# main.net
KiCad netlist of a schematic drawn in EAGLE
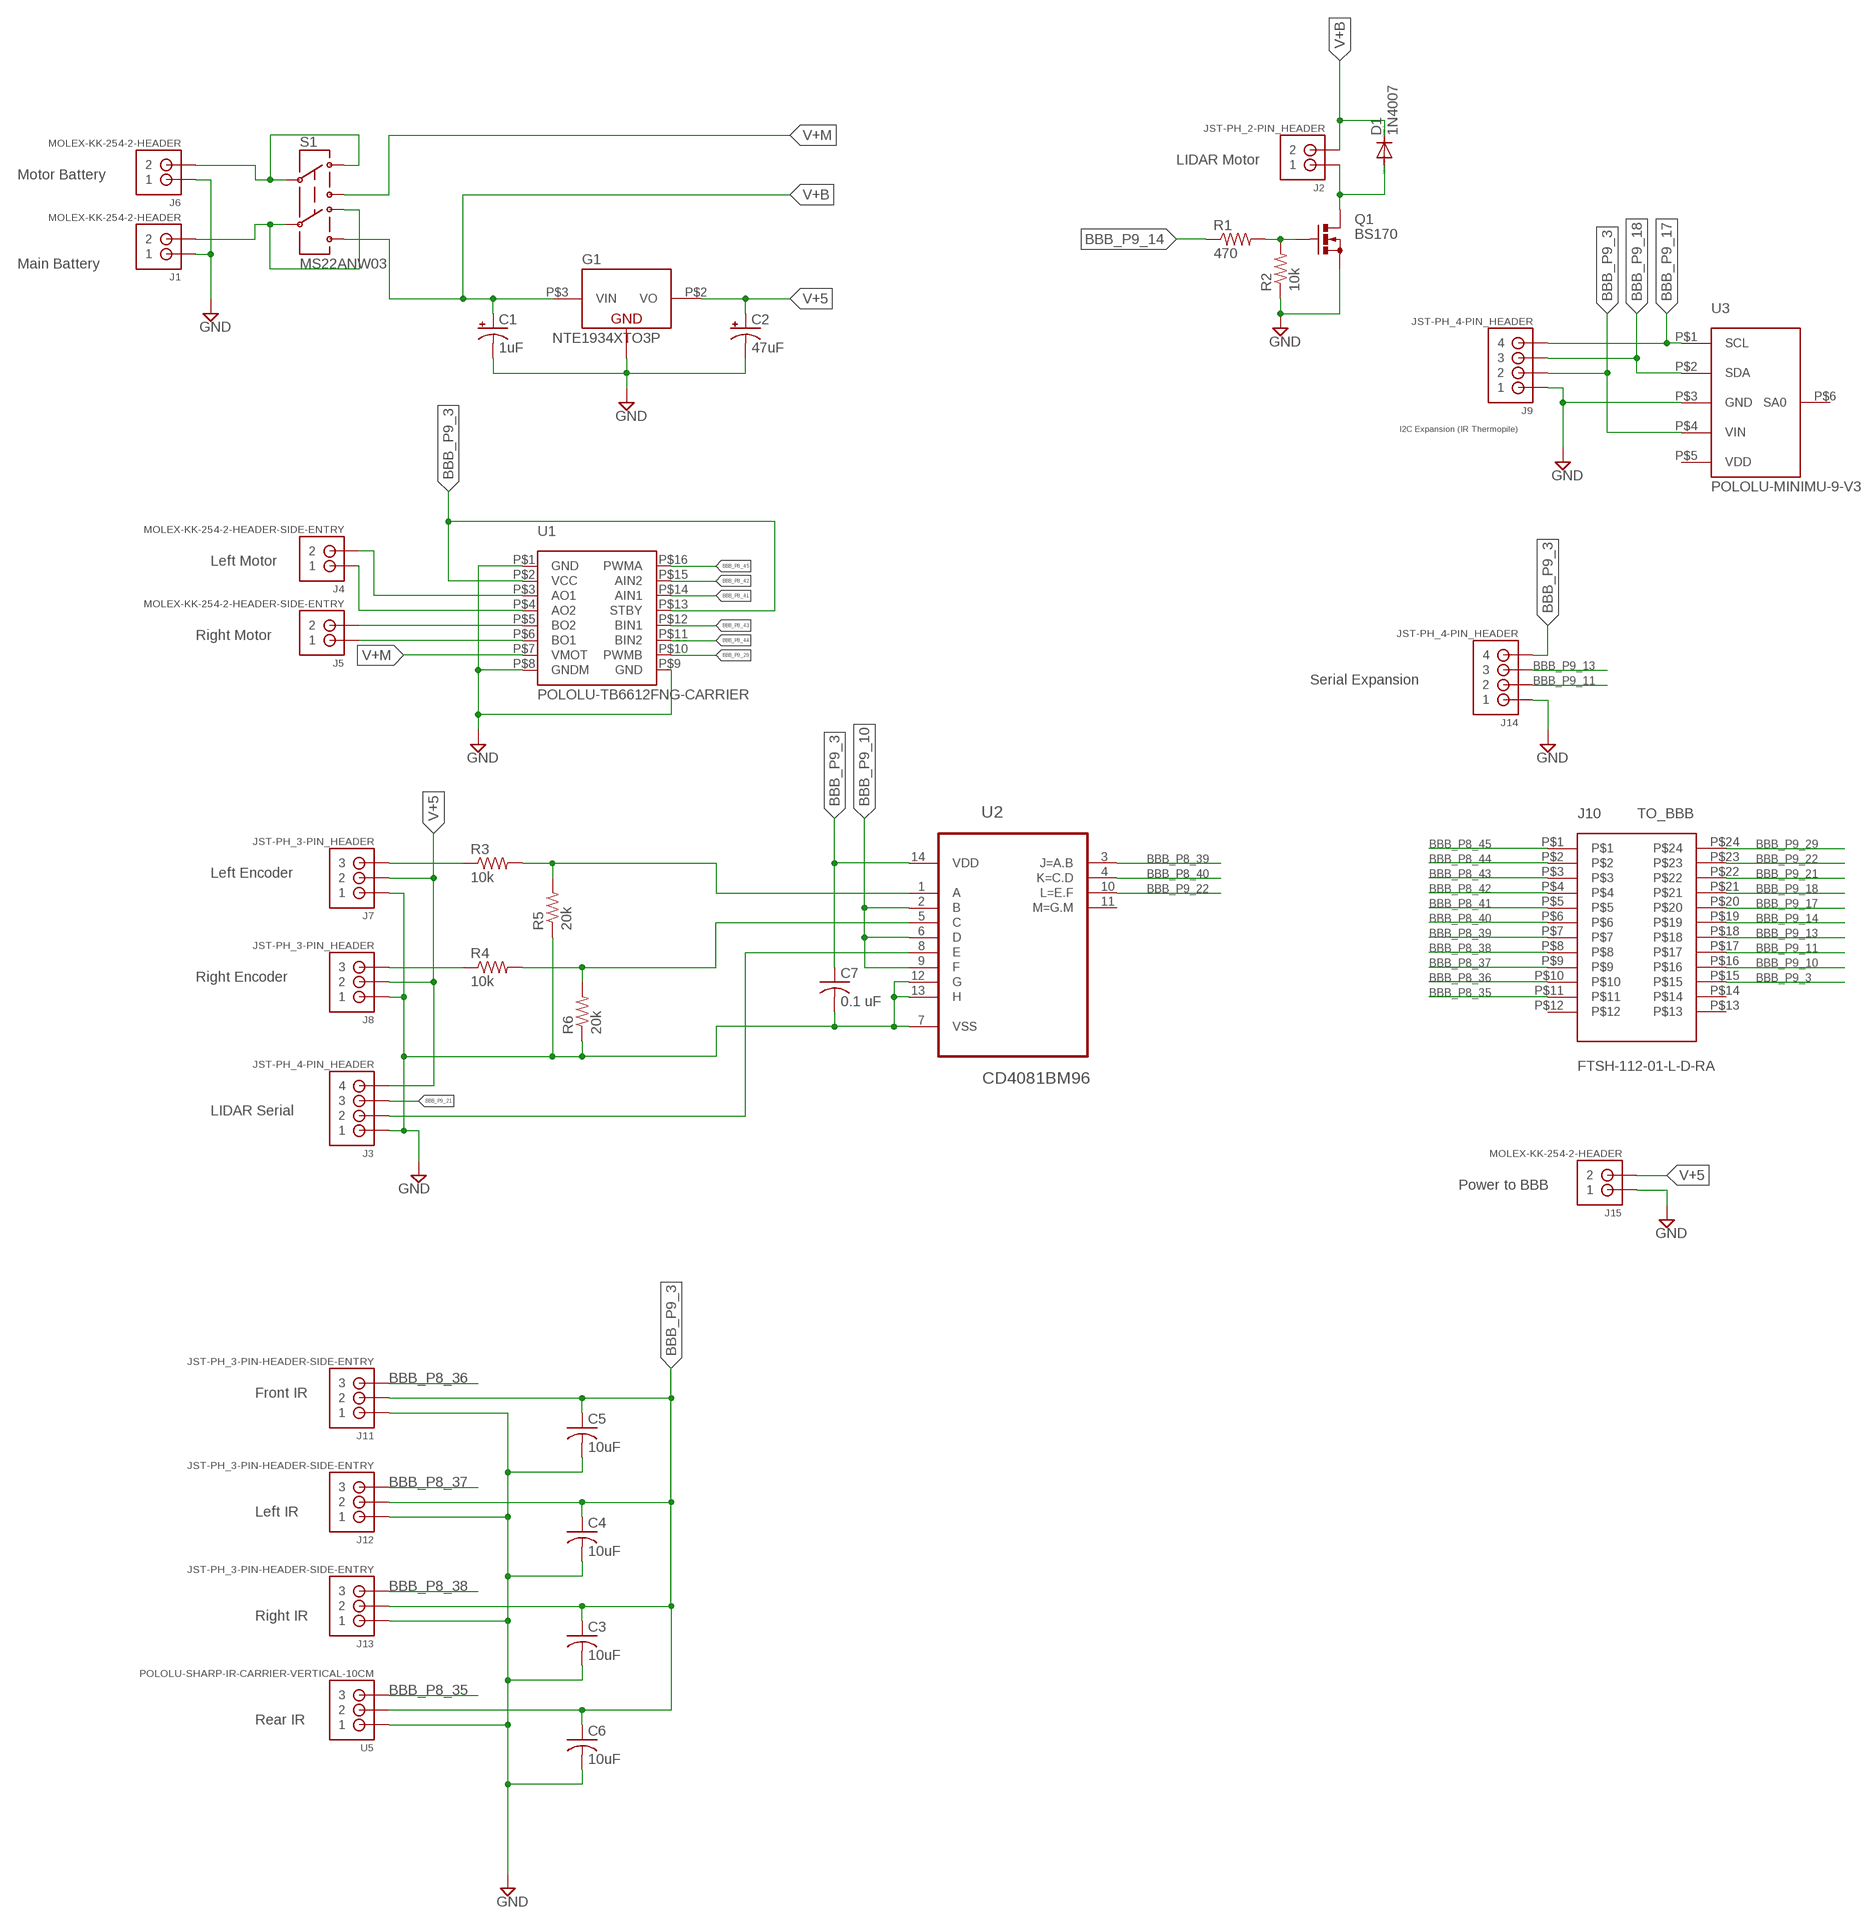
[diagram p0: schematic, sheet 1]

(export (version "E")
  (design (tool "Eeschema 10.0.6"))
  (components
    (comp (ref "C1")
      (value "1uF")
      (footprint "eagle-import:PANASONIC_B")
      (libsource (lib "eagle-import") (part "CPOL-USB"))
    )
    (comp (ref "C2")
      (value "47uF")
      (footprint "eagle-import:PANASONIC_C")
      (libsource (lib "eagle-import") (part "CPOL-USC"))
    )
    (comp (ref "C3")
      (value "10uF")
      (footprint "eagle-import:C0603")
      (libsource (lib "eagle-import") (part "resistor_C-USC0603"))
    )
    (comp (ref "C4")
      (value "10uF")
      (footprint "eagle-import:C0603")
      (libsource (lib "eagle-import") (part "resistor_C-USC0603"))
    )
    (comp (ref "C5")
      (value "10uF")
      (footprint "eagle-import:C0603")
      (libsource (lib "eagle-import") (part "resistor_C-USC0603"))
    )
    (comp (ref "C6")
      (value "10uF")
      (footprint "eagle-import:C0603")
      (libsource (lib "eagle-import") (part "resistor_C-USC0603"))
    )
    (comp (ref "C7")
      (value "0.1 uF")
      (footprint "eagle-import:C0603")
      (libsource (lib "eagle-import") (part "C-USC0603"))
    )
    (comp (ref "D1")
      (value "1N4007")
      (footprint "eagle-import:DO41-10")
      (libsource (lib "eagle-import") (part "1N4004"))
    )
    (comp (ref "G1")
      (value "NTE1934XTO3P")
      (footprint "eagle-import:TO3P")
      (libsource (lib "eagle-import") (part "NTE1934XTO3P"))
    )
    (comp (ref "J1")
      (value "MOLEX-KK-254-2-HEADER")
      (footprint "eagle-import:MOLEX-KK-254-2-HEADER")
      (libsource (lib "eagle-import") (part "MOLEX-KK-254-2-HEADER"))
    )
    (comp (ref "J2")
      (value "JST-PH_2-PIN_HEADER")
      (footprint "eagle-import:JST_B2B-PH_HEADER")
      (libsource (lib "eagle-import") (part "JST-PH_2-PIN_HEADER"))
    )
    (comp (ref "J3")
      (value "JST-PH_4-PIN_HEADER")
      (footprint "eagle-import:JST_B4B-PH_HEADER")
      (libsource (lib "eagle-import") (part "JST-PH_4-PIN_HEADER"))
    )
    (comp (ref "J4")
      (value "MOLEX-KK-254-2-HEADER-SIDE-ENTRY")
      (footprint "eagle-import:MOLEX-KK-254-2-HEADER-SIDE-ENTRY")
      (libsource (lib "eagle-import") (part "MOLEX-KK-254-2-HEADER-SIDE-ENTRY"))
    )
    (comp (ref "J5")
      (value "MOLEX-KK-254-2-HEADER-SIDE-ENTRY")
      (footprint "eagle-import:MOLEX-KK-254-2-HEADER-SIDE-ENTRY")
      (libsource (lib "eagle-import") (part "MOLEX-KK-254-2-HEADER-SIDE-ENTRY"))
    )
    (comp (ref "J6")
      (value "MOLEX-KK-254-2-HEADER")
      (footprint "eagle-import:MOLEX-KK-254-2-HEADER")
      (libsource (lib "eagle-import") (part "MOLEX-KK-254-2-HEADER"))
    )
    (comp (ref "J7")
      (value "JST-PH_3-PIN_HEADER")
      (footprint "eagle-import:JST_B3B-PH_HEADER")
      (libsource (lib "eagle-import") (part "JST-PH_3-PIN_HEADER"))
    )
    (comp (ref "J8")
      (value "JST-PH_3-PIN_HEADER")
      (footprint "eagle-import:JST_B3B-PH_HEADER")
      (libsource (lib "eagle-import") (part "JST-PH_3-PIN_HEADER"))
    )
    (comp (ref "J9")
      (value "JST-PH_4-PIN_HEADER")
      (footprint "eagle-import:JST_B4B-PH_HEADER")
      (libsource (lib "eagle-import") (part "JST-PH_4-PIN_HEADER"))
    )
    (comp (ref "J10")
      (value "FTSH-112-01-L-D-RA")
      (footprint "eagle-import:FTSH-112-01-L-D-RA")
      (libsource (lib "eagle-import") (part "FTSH-112-CONNRIGHT-ANGLE"))
    )
    (comp (ref "J11")
      (value "JST-PH_3-PIN-HEADER-SIDE-ENTRY")
      (footprint "eagle-import:JST-S3B-PH-K-S")
      (libsource (lib "eagle-import") (part "JST-PH_3-PIN-HEADER-SIDE-ENTRY"))
    )
    (comp (ref "J12")
      (value "JST-PH_3-PIN-HEADER-SIDE-ENTRY")
      (footprint "eagle-import:JST-S3B-PH-K-S")
      (libsource (lib "eagle-import") (part "JST-PH_3-PIN-HEADER-SIDE-ENTRY"))
    )
    (comp (ref "J13")
      (value "JST-PH_3-PIN-HEADER-SIDE-ENTRY")
      (footprint "eagle-import:JST-S3B-PH-K-S")
      (libsource (lib "eagle-import") (part "JST-PH_3-PIN-HEADER-SIDE-ENTRY"))
    )
    (comp (ref "J14")
      (value "JST-PH_4-PIN_HEADER")
      (footprint "eagle-import:JST_B4B-PH_HEADER")
      (libsource (lib "eagle-import") (part "JST-PH_4-PIN_HEADER"))
    )
    (comp (ref "J15")
      (value "MOLEX-KK-254-2-HEADER")
      (footprint "eagle-import:MOLEX-KK-254-2-HEADER")
      (libsource (lib "eagle-import") (part "MOLEX-KK-254-2-HEADER"))
    )
    (comp (ref "Q1")
      (value "BS170")
      (footprint "eagle-import:SOT54E")
      (libsource (lib "eagle-import") (part "BS170"))
    )
    (comp (ref "R1")
      (value "470")
      (footprint "eagle-import:R0402")
      (libsource (lib "eagle-import") (part "R-US_R0402"))
    )
    (comp (ref "R2")
      (value "10k")
      (footprint "eagle-import:R0402")
      (libsource (lib "eagle-import") (part "R-US_R0402"))
    )
    (comp (ref "R3")
      (value "10k")
      (footprint "eagle-import:R0402")
      (libsource (lib "eagle-import") (part "resistor_R-US_R0402"))
    )
    (comp (ref "R4")
      (value "10k")
      (footprint "eagle-import:R0402")
      (libsource (lib "eagle-import") (part "resistor_R-US_R0402"))
    )
    (comp (ref "R5")
      (value "20k")
      (footprint "eagle-import:R0402")
      (libsource (lib "eagle-import") (part "resistor_R-US_R0402"))
    )
    (comp (ref "R6")
      (value "20k")
      (footprint "eagle-import:R0402")
      (libsource (lib "eagle-import") (part "resistor_R-US_R0402"))
    )
    (comp (ref "S1")
      (value "MS22ANW03")
      (footprint "eagle-import:SWITCH-DPDT-NKK-MS22ANW03")
      (libsource (lib "eagle-import") (part "SWITCH-DPDT-NKK-MS22ANW03NKK-MS22ANW03"))
    )
    (comp (ref "U1")
      (value "POLOLU-TB6612FNG-CARRIER")
      (footprint "eagle-import:POLOLU-TB6612FNG-CARRIER")
      (libsource (lib "eagle-import") (part "POLOLU-TB6612FNG-CARRIER"))
    )
    (comp (ref "U2")
      (value "CD4081BM96")
      (footprint "eagle-import:SO14")
      (libsource (lib "eagle-import") (part "CD4081BESO-14"))
    )
    (comp (ref "U3")
      (value "POLOLU-MINIMU-9-V3")
      (footprint "eagle-import:POLOLU-MINIMU-9-V3")
      (libsource (lib "eagle-import") (part "POLOLU-MINIMU-9-V3"))
    )
    (comp (ref "U5")
      (value "POLOLU-SHARP-IR-CARRIER-VERTICAL-10CM")
      (footprint "eagle-import:POLOLU-SHARP-IR-CARRIER-VERTICAL-GP2Y0D8__Z0F")
      (libsource (lib "eagle-import") (part "POLOLU-SHARP-IR-CARRIER-VERTICAL-10CM"))
    )
  )
  (nets
    (net (code "1") (name "/BBB_P8_35") (class "Default")
      (node (ref "J10") (pin "P$11") (pinfunction "P$11_P$11") (pintype "bidirectional"))
      (node (ref "U5") (pin "P$3") (pinfunction "3_P$3") (pintype "bidirectional"))
    )
    (net (code "2") (name "/BBB_P8_36") (class "Default")
      (node (ref "J10") (pin "P$10") (pinfunction "P$10_P$10") (pintype "bidirectional"))
      (node (ref "J11") (pin "P$3") (pinfunction "3_P$3") (pintype "bidirectional"))
    )
    (net (code "3") (name "/BBB_P8_37") (class "Default")
      (node (ref "J10") (pin "P$9") (pinfunction "P$9_P$9") (pintype "bidirectional"))
      (node (ref "J12") (pin "P$3") (pinfunction "3_P$3") (pintype "bidirectional"))
    )
    (net (code "4") (name "/BBB_P8_38") (class "Default")
      (node (ref "J10") (pin "P$8") (pinfunction "P$8_P$8") (pintype "bidirectional"))
      (node (ref "J13") (pin "P$3") (pinfunction "3_P$3") (pintype "bidirectional"))
    )
    (net (code "5") (name "/BBB_P8_39") (class "Default")
      (node (ref "J10") (pin "P$7") (pinfunction "P$7_P$7") (pintype "bidirectional"))
      (node (ref "U2") (pin "3") (pinfunction "J=A.B_3") (pintype "output"))
    )
    (net (code "6") (name "/BBB_P8_40") (class "Default")
      (node (ref "J10") (pin "P$6") (pinfunction "P$6_P$6") (pintype "bidirectional"))
      (node (ref "U2") (pin "4") (pinfunction "K=C.D_4") (pintype "output"))
    )
    (net (code "7") (name "/BBB_P9_11") (class "Default")
      (node (ref "J10") (pin "P$17") (pinfunction "P$17_P$17") (pintype "bidirectional"))
      (node (ref "J14") (pin "P2") (pinfunction "2_P2") (pintype "bidirectional"))
    )
    (net (code "8") (name "/BBB_P9_13") (class "Default")
      (node (ref "J10") (pin "P$18") (pinfunction "P$18_P$18") (pintype "bidirectional"))
      (node (ref "J14") (pin "P3") (pinfunction "3_P3") (pintype "bidirectional"))
    )
    (net (code "9") (name "/BBB_P9_22") (class "Default")
      (node (ref "J10") (pin "P$23") (pinfunction "P$23_P$23") (pintype "bidirectional"))
      (node (ref "U2") (pin "10") (pinfunction "L=E.F_10") (pintype "output"))
    )
    (net (code "10") (name "/VDD") (class "Default")
      (node (ref "U3") (pin "P$5") (pinfunction "VDD_P$5") (pintype "power_in"))
    )
    (net (code "11") (name "BBB_P8_41") (class "Default")
      (node (ref "J10") (pin "P$5") (pinfunction "P$5_P$5") (pintype "bidirectional"))
      (node (ref "U1") (pin "P$14") (pinfunction "AIN1_P$14") (pintype "input"))
    )
    (net (code "12") (name "BBB_P8_42") (class "Default")
      (node (ref "J10") (pin "P$4") (pinfunction "P$4_P$4") (pintype "bidirectional"))
      (node (ref "U1") (pin "P$15") (pinfunction "AIN2_P$15") (pintype "input"))
    )
    (net (code "13") (name "BBB_P8_43") (class "Default")
      (node (ref "J10") (pin "P$3") (pinfunction "P$3_P$3") (pintype "bidirectional"))
      (node (ref "U1") (pin "P$12") (pinfunction "BIN1_P$12") (pintype "input"))
    )
    (net (code "14") (name "BBB_P8_44") (class "Default")
      (node (ref "J10") (pin "P$2") (pinfunction "P$2_P$2") (pintype "bidirectional"))
      (node (ref "U1") (pin "P$11") (pinfunction "BIN2_P$11") (pintype "input"))
    )
    (net (code "15") (name "BBB_P8_45") (class "Default")
      (node (ref "J10") (pin "P$1") (pinfunction "P$1_P$1") (pintype "bidirectional"))
      (node (ref "U1") (pin "P$16") (pinfunction "PWMA_P$16") (pintype "input"))
    )
    (net (code "16") (name "BBB_P9_3") (class "Default")
      (node (ref "C3") (pin "1") (pinfunction "1_1") (pintype "passive"))
      (node (ref "C4") (pin "1") (pinfunction "1_1") (pintype "passive"))
      (node (ref "C5") (pin "1") (pinfunction "1_1") (pintype "passive"))
      (node (ref "C6") (pin "1") (pinfunction "1_1") (pintype "passive"))
      (node (ref "C7") (pin "1") (pinfunction "1_1") (pintype "passive"))
      (node (ref "J10") (pin "P$15") (pinfunction "P$15_P$15") (pintype "bidirectional"))
      (node (ref "J11") (pin "P$2") (pinfunction "2_P$2") (pintype "bidirectional"))
      (node (ref "J12") (pin "P$2") (pinfunction "2_P$2") (pintype "bidirectional"))
      (node (ref "J13") (pin "P$2") (pinfunction "2_P$2") (pintype "bidirectional"))
      (node (ref "J14") (pin "P4") (pinfunction "4_P4") (pintype "bidirectional"))
      (node (ref "J9") (pin "P2") (pinfunction "2_P2") (pintype "bidirectional"))
      (node (ref "U1") (pin "P$13") (pinfunction "STBY_P$13") (pintype "input"))
      (node (ref "U1") (pin "P$2") (pinfunction "VCC_P$2") (pintype "power_in"))
      (node (ref "U2") (pin "14") (pinfunction "VDD_14") (pintype "power_in"))
      (node (ref "U3") (pin "P$4") (pinfunction "VIN_P$4") (pintype "power_in"))
      (node (ref "U5") (pin "P$2") (pinfunction "2_P$2") (pintype "bidirectional"))
    )
    (net (code "17") (name "BBB_P9_10") (class "Default")
      (node (ref "J10") (pin "P$16") (pinfunction "P$16_P$16") (pintype "bidirectional"))
      (node (ref "U2") (pin "2") (pinfunction "B_2") (pintype "input"))
      (node (ref "U2") (pin "6") (pinfunction "D_6") (pintype "input"))
      (node (ref "U2") (pin "9") (pinfunction "F_9") (pintype "input"))
    )
    (net (code "18") (name "BBB_P9_14") (class "Default")
      (node (ref "J10") (pin "P$19") (pinfunction "P$19_P$19") (pintype "bidirectional"))
      (node (ref "R1") (pin "1") (pinfunction "1_1") (pintype "passive"))
    )
    (net (code "19") (name "BBB_P9_17") (class "Default")
      (node (ref "J10") (pin "P$20") (pinfunction "P$20_P$20") (pintype "bidirectional"))
      (node (ref "J9") (pin "P4") (pinfunction "4_P4") (pintype "bidirectional"))
      (node (ref "U3") (pin "P$1") (pinfunction "SCL_P$1") (pintype "bidirectional"))
    )
    (net (code "20") (name "BBB_P9_18") (class "Default")
      (node (ref "J10") (pin "P$21") (pinfunction "P$21_P$21") (pintype "bidirectional"))
      (node (ref "J9") (pin "P3") (pinfunction "3_P3") (pintype "bidirectional"))
      (node (ref "U3") (pin "P$2") (pinfunction "SDA_P$2") (pintype "bidirectional"))
    )
    (net (code "21") (name "BBB_P9_21") (class "Default")
      (node (ref "J10") (pin "P$22") (pinfunction "P$22_P$22") (pintype "bidirectional"))
      (node (ref "J3") (pin "P3") (pinfunction "3_P3") (pintype "bidirectional"))
    )
    (net (code "22") (name "BBB_P9_29") (class "Default")
      (node (ref "J10") (pin "P$24") (pinfunction "P$24_P$24") (pintype "bidirectional"))
      (node (ref "U1") (pin "P$10") (pinfunction "PWMB_P$10") (pintype "input"))
    )
    (net (code "23") (name "GND") (class "Default")
      (node (ref "C1") (pin "-") (pinfunction "-_-") (pintype "passive"))
      (node (ref "C2") (pin "-") (pinfunction "-_-") (pintype "passive"))
      (node (ref "C3") (pin "2") (pinfunction "2_2") (pintype "passive"))
      (node (ref "C4") (pin "2") (pinfunction "2_2") (pintype "passive"))
      (node (ref "C5") (pin "2") (pinfunction "2_2") (pintype "passive"))
      (node (ref "C6") (pin "2") (pinfunction "2_2") (pintype "passive"))
      (node (ref "C7") (pin "2") (pinfunction "2_2") (pintype "passive"))
      (node (ref "G1") (pin "P$1") (pinfunction "GND_P$1") (pintype "bidirectional"))
      (node (ref "J1") (pin "P$1") (pinfunction "1_P$1") (pintype "bidirectional"))
      (node (ref "J11") (pin "P$1") (pinfunction "1_P$1") (pintype "bidirectional"))
      (node (ref "J12") (pin "P$1") (pinfunction "1_P$1") (pintype "bidirectional"))
      (node (ref "J13") (pin "P$1") (pinfunction "1_P$1") (pintype "bidirectional"))
      (node (ref "J14") (pin "P1") (pinfunction "1_P1") (pintype "bidirectional"))
      (node (ref "J15") (pin "P$1") (pinfunction "1_P$1") (pintype "bidirectional"))
      (node (ref "J3") (pin "P1") (pinfunction "1_P1") (pintype "bidirectional"))
      (node (ref "J6") (pin "P$1") (pinfunction "1_P$1") (pintype "bidirectional"))
      (node (ref "J7") (pin "P1") (pinfunction "1_P1") (pintype "bidirectional"))
      (node (ref "J8") (pin "P1") (pinfunction "1_P1") (pintype "bidirectional"))
      (node (ref "J9") (pin "P1") (pinfunction "1_P1") (pintype "bidirectional"))
      (node (ref "Q1") (pin "S") (pinfunction "S_S") (pintype "passive"))
      (node (ref "R2") (pin "1") (pinfunction "1_1") (pintype "passive"))
      (node (ref "R5") (pin "1") (pinfunction "1_1") (pintype "passive"))
      (node (ref "R6") (pin "1") (pinfunction "1_1") (pintype "passive"))
      (node (ref "U1") (pin "P$1") (pinfunction "GND_P$1") (pintype "power_in"))
      (node (ref "U1") (pin "P$8") (pinfunction "GNDM_P$8") (pintype "power_in"))
      (node (ref "U1") (pin "P$9") (pinfunction "GND_P$9") (pintype "power_in"))
      (node (ref "U2") (pin "12") (pinfunction "G_12") (pintype "input"))
      (node (ref "U2") (pin "13") (pinfunction "H_13") (pintype "input"))
      (node (ref "U2") (pin "7") (pinfunction "VSS_7") (pintype "power_in"))
      (node (ref "U3") (pin "P$3") (pinfunction "GND_P$3") (pintype "power_in"))
      (node (ref "U5") (pin "P$1") (pinfunction "1_P$1") (pintype "bidirectional"))
    )
    (net (code "24") (name "Net-(J1-2)") (class "Default")
      (node (ref "J1") (pin "P$2") (pinfunction "2_P$2") (pintype "bidirectional"))
      (node (ref "S1") (pin "P$4") (pinfunction "4_P$4") (pintype "bidirectional"))
      (node (ref "S1") (pin "P$5") (pinfunction "5_P$5") (pintype "bidirectional"))
    )
    (net (code "25") (name "Net-(J2-1)") (class "Default")
      (node (ref "D1") (pin "A") (pinfunction "A_A") (pintype "passive"))
      (node (ref "J2") (pin "P1") (pinfunction "1_P1") (pintype "bidirectional"))
      (node (ref "Q1") (pin "D") (pinfunction "D_D") (pintype "passive"))
    )
    (net (code "26") (name "Net-(J3-2)") (class "Default")
      (node (ref "J3") (pin "P2") (pinfunction "2_P2") (pintype "bidirectional"))
      (node (ref "U2") (pin "8") (pinfunction "E_8") (pintype "input"))
    )
    (net (code "27") (name "Net-(J4-1)") (class "Default")
      (node (ref "J4") (pin "P$1") (pinfunction "1_P$1") (pintype "bidirectional"))
      (node (ref "U1") (pin "P$4") (pinfunction "AO2_P$4") (pintype "output"))
    )
    (net (code "28") (name "Net-(J4-2)") (class "Default")
      (node (ref "J4") (pin "P$2") (pinfunction "2_P$2") (pintype "bidirectional"))
      (node (ref "U1") (pin "P$3") (pinfunction "AO1_P$3") (pintype "output"))
    )
    (net (code "29") (name "Net-(J5-1)") (class "Default")
      (node (ref "J5") (pin "P$1") (pinfunction "1_P$1") (pintype "bidirectional"))
      (node (ref "U1") (pin "P$6") (pinfunction "BO1_P$6") (pintype "output"))
    )
    (net (code "30") (name "Net-(J5-2)") (class "Default")
      (node (ref "J5") (pin "P$2") (pinfunction "2_P$2") (pintype "bidirectional"))
      (node (ref "U1") (pin "P$5") (pinfunction "BO2_P$5") (pintype "output"))
    )
    (net (code "31") (name "Net-(J6-2)") (class "Default")
      (node (ref "J6") (pin "P$2") (pinfunction "2_P$2") (pintype "bidirectional"))
      (node (ref "S1") (pin "P$1") (pinfunction "1_P$1") (pintype "bidirectional"))
      (node (ref "S1") (pin "P$2") (pinfunction "2_P$2") (pintype "bidirectional"))
    )
    (net (code "32") (name "Net-(J7-3)") (class "Default")
      (node (ref "J7") (pin "P3") (pinfunction "3_P3") (pintype "bidirectional"))
      (node (ref "R3") (pin "1") (pinfunction "1_1") (pintype "passive"))
    )
    (net (code "33") (name "Net-(J8-3)") (class "Default")
      (node (ref "J8") (pin "P3") (pinfunction "3_P3") (pintype "bidirectional"))
      (node (ref "R4") (pin "1") (pinfunction "1_1") (pintype "passive"))
    )
    (net (code "34") (name "Net-(Q1-PadG)") (class "Default")
      (node (ref "Q1") (pin "G") (pinfunction "G_G") (pintype "passive"))
      (node (ref "R1") (pin "2") (pinfunction "2_2") (pintype "passive"))
      (node (ref "R2") (pin "2") (pinfunction "2_2") (pintype "passive"))
    )
    (net (code "35") (name "Net-(U2-A)") (class "Default")
      (node (ref "R3") (pin "2") (pinfunction "2_2") (pintype "passive"))
      (node (ref "R5") (pin "2") (pinfunction "2_2") (pintype "passive"))
      (node (ref "U2") (pin "1") (pinfunction "A_1") (pintype "input"))
    )
    (net (code "36") (name "Net-(U2-C)") (class "Default")
      (node (ref "R4") (pin "2") (pinfunction "2_2") (pintype "passive"))
      (node (ref "R6") (pin "2") (pinfunction "2_2") (pintype "passive"))
      (node (ref "U2") (pin "5") (pinfunction "C_5") (pintype "input"))
    )
    (net (code "37") (name "V+5") (class "Default")
      (node (ref "C2") (pin "+") (pinfunction "+_+") (pintype "passive"))
      (node (ref "G1") (pin "P$2") (pinfunction "VO_P$2") (pintype "bidirectional"))
      (node (ref "J15") (pin "P$2") (pinfunction "2_P$2") (pintype "bidirectional"))
      (node (ref "J3") (pin "P4") (pinfunction "4_P4") (pintype "bidirectional"))
      (node (ref "J7") (pin "P2") (pinfunction "2_P2") (pintype "bidirectional"))
      (node (ref "J8") (pin "P2") (pinfunction "2_P2") (pintype "bidirectional"))
    )
    (net (code "38") (name "V+B") (class "Default")
      (node (ref "C1") (pin "+") (pinfunction "+_+") (pintype "passive"))
      (node (ref "D1") (pin "C") (pinfunction "C_C") (pintype "passive"))
      (node (ref "G1") (pin "P$3") (pinfunction "VIN_P$3") (pintype "bidirectional"))
      (node (ref "J2") (pin "P2") (pinfunction "2_P2") (pintype "bidirectional"))
      (node (ref "S1") (pin "P$6") (pinfunction "6_P$6") (pintype "bidirectional"))
    )
    (net (code "39") (name "V+M") (class "Default")
      (node (ref "S1") (pin "P$3") (pinfunction "3_P$3") (pintype "bidirectional"))
      (node (ref "U1") (pin "P$7") (pinfunction "VMOT_P$7") (pintype "power_in"))
    )
    (net (code "40") (name "unconnected-(J10-PadP$12)") (class "Default")
      (node (ref "J10") (pin "P$12") (pinfunction "P$12_P$12") (pintype "bidirectional"))
    )
    (net (code "41") (name "unconnected-(J10-PadP$13)") (class "Default")
      (node (ref "J10") (pin "P$13") (pinfunction "P$13_P$13") (pintype "bidirectional"))
    )
    (net (code "42") (name "unconnected-(J10-PadP$14)") (class "Default")
      (node (ref "J10") (pin "P$14") (pinfunction "P$14_P$14") (pintype "bidirectional"))
    )
    (net (code "43") (name "unconnected-(U2-M=G.M-Pad11)") (class "Default")
      (node (ref "U2") (pin "11") (pinfunction "M=G.M_11") (pintype "output"))
    )
    (net (code "44") (name "unconnected-(U3-SA0-PadP$6)") (class "Default")
      (node (ref "U3") (pin "P$6") (pinfunction "SA0_P$6") (pintype "input"))
    )
  )
)
